# usbtinyisp.net
KiCad netlist of a schematic drawn in EAGLE
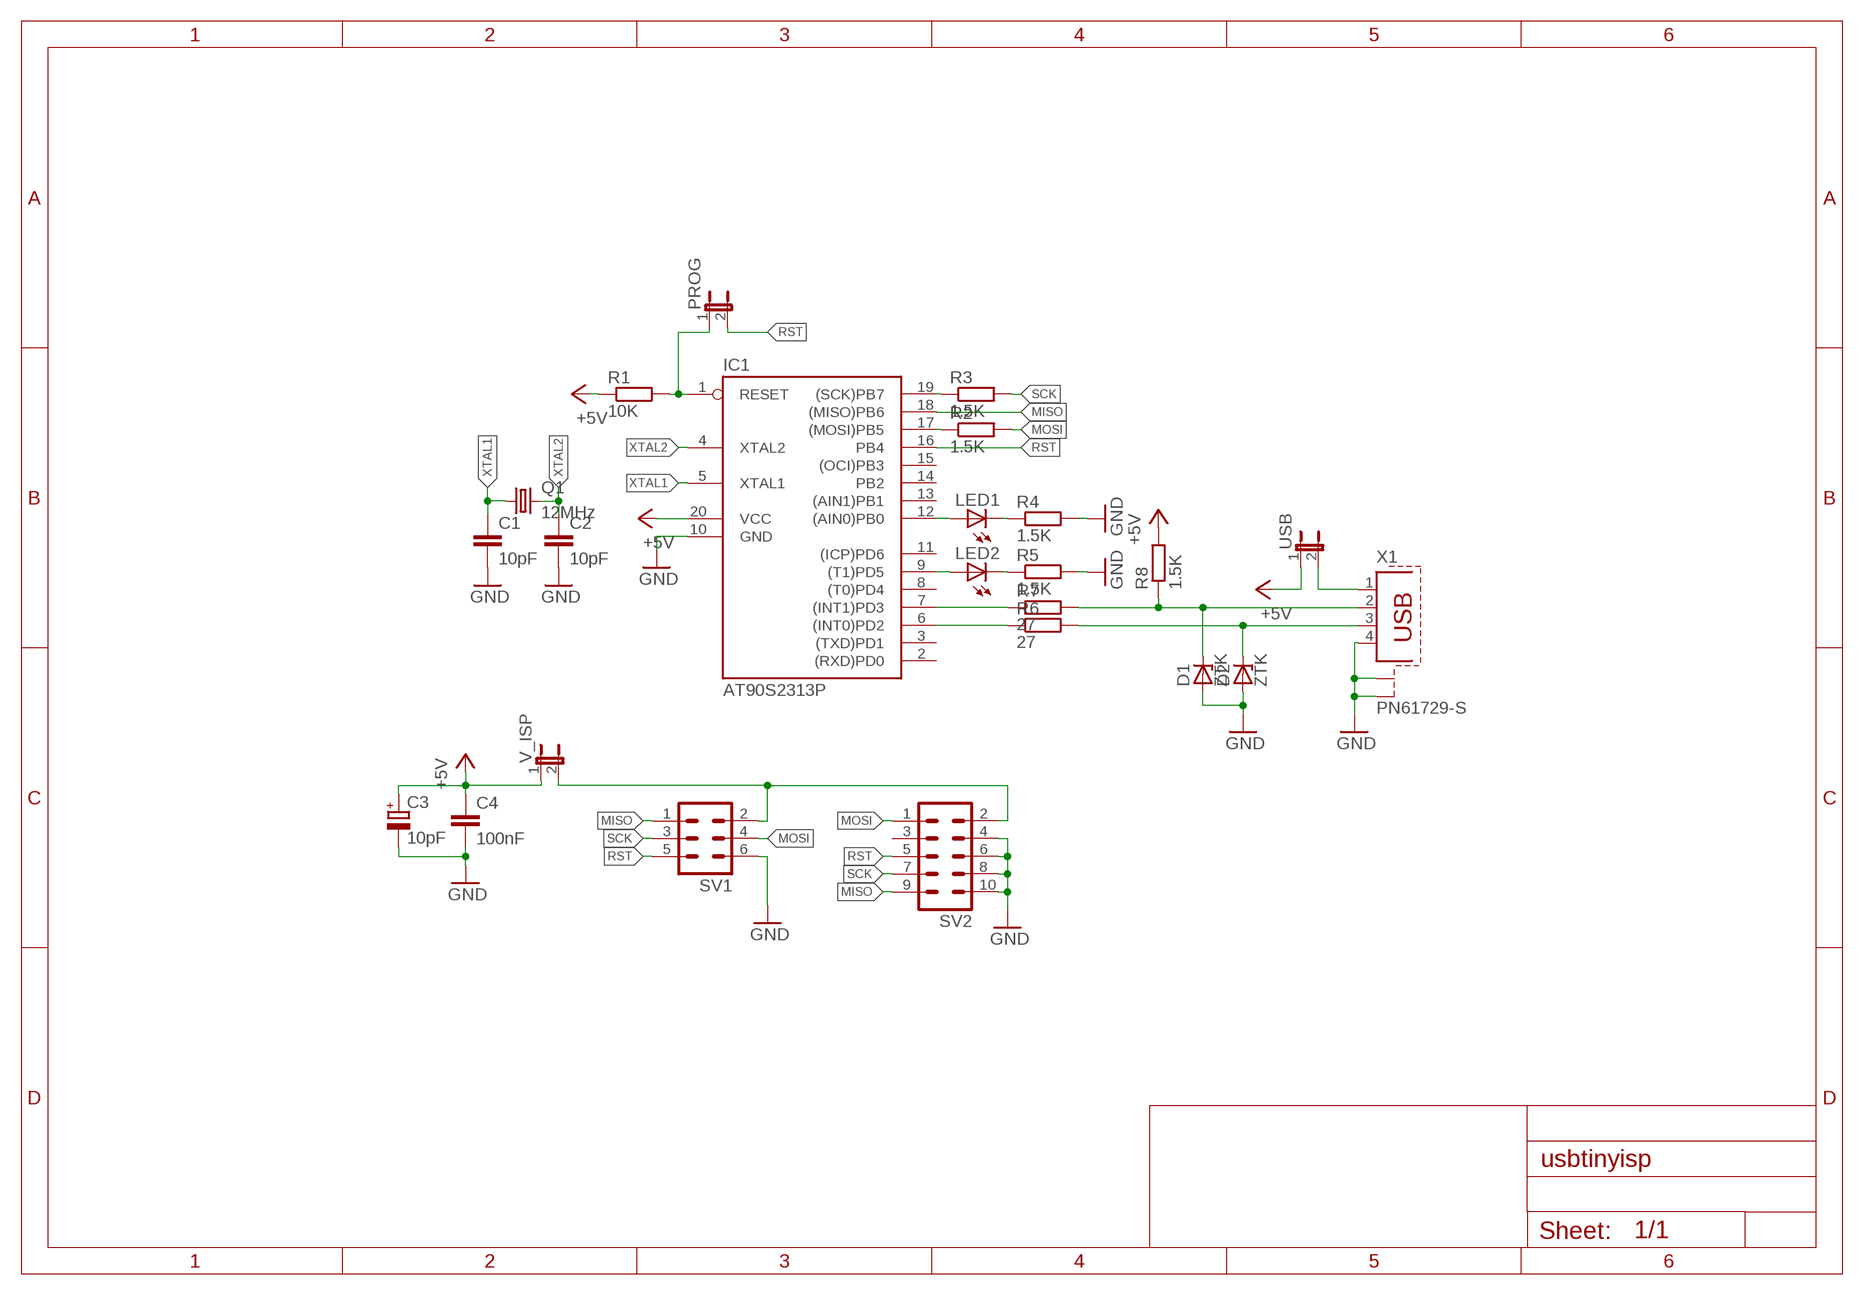
[diagram p0: schematic, sheet 1]

(export (version "E")
  (design (tool "Eeschema 10.0.6"))
  (components
    (comp (ref "C1")
      (value "10pF")
      (footprint "eagle-import:C025-025X050")
      (libsource (lib "eagle-import") (part "C-EU025-025X050"))
    )
    (comp (ref "C2")
      (value "10pF")
      (footprint "eagle-import:C025-025X050")
      (libsource (lib "eagle-import") (part "C-EU025-025X050"))
    )
    (comp (ref "C3")
      (value "10pF")
      (footprint "eagle-import:E2,5-6E")
      (libsource (lib "eagle-import") (part "CPOL-EUE2,5-6E"))
    )
    (comp (ref "C4")
      (value "100nF")
      (footprint "eagle-import:C025-025X050")
      (libsource (lib "eagle-import") (part "C-EU025-025X050"))
    )
    (comp (ref "D1")
      (value "ZTK")
      (footprint "eagle-import:DO35Z10")
      (libsource (lib "eagle-import") (part "ZTK"))
    )
    (comp (ref "D2")
      (value "ZTK")
      (footprint "eagle-import:DO35Z10")
      (libsource (lib "eagle-import") (part "ZTK"))
    )
    (comp (ref "IC1")
      (value "AT90S2313P")
      (footprint "eagle-import:DIL20")
      (libsource (lib "eagle-import") (part "AT90S2313P"))
    )
    (comp (ref "LED1")
      (value "LED3MM")
      (footprint "eagle-import:LED3MM")
      (libsource (lib "eagle-import") (part "LED3MM"))
    )
    (comp (ref "LED2")
      (value "LED3MM")
      (footprint "eagle-import:LED3MM")
      (libsource (lib "eagle-import") (part "LED3MM"))
    )
    (comp (ref "PROG")
      (value "JP1E")
      (footprint "eagle-import:JP1")
      (libsource (lib "eagle-import") (part "JP1E"))
    )
    (comp (ref "Q1")
      (value "12MHz")
      (footprint "eagle-import:HC49U70")
      (libsource (lib "eagle-import") (part "CRYSTALHC49U70"))
    )
    (comp (ref "R1")
      (value "10K")
      (footprint "eagle-import:0207_7")
      (libsource (lib "eagle-import") (part "R-EU_0207/7"))
    )
    (comp (ref "R2")
      (value "1.5K")
      (footprint "eagle-import:0207_7")
      (libsource (lib "eagle-import") (part "R-EU_0207/7"))
    )
    (comp (ref "R3")
      (value "1.5K")
      (footprint "eagle-import:0207_7")
      (libsource (lib "eagle-import") (part "R-EU_0207/7"))
    )
    (comp (ref "R4")
      (value "1.5K")
      (footprint "eagle-import:0207_7")
      (libsource (lib "eagle-import") (part "R-EU_0207/7"))
    )
    (comp (ref "R5")
      (value "1.5K")
      (footprint "eagle-import:0207_7")
      (libsource (lib "eagle-import") (part "R-EU_0207/7"))
    )
    (comp (ref "R6")
      (value "27")
      (footprint "eagle-import:0207_7")
      (libsource (lib "eagle-import") (part "R-EU_0207/7"))
    )
    (comp (ref "R7")
      (value "27")
      (footprint "eagle-import:0207_7")
      (libsource (lib "eagle-import") (part "R-EU_0207/7"))
    )
    (comp (ref "R8")
      (value "1.5K")
      (footprint "eagle-import:0207_7")
      (libsource (lib "eagle-import") (part "R-EU_0207/7"))
    )
    (comp (ref "SV1")
      (value "MA03-2")
      (footprint "eagle-import:MA03-2")
      (libsource (lib "eagle-import") (part "MA03-2"))
    )
    (comp (ref "SV2")
      (value "MA05-2")
      (footprint "eagle-import:MA05-2")
      (libsource (lib "eagle-import") (part "MA05-2"))
    )
    (comp (ref "USB")
      (value "JP1E")
      (footprint "eagle-import:JP1")
      (libsource (lib "eagle-import") (part "JP1E"))
    )
    (comp (ref "V_ISP")
      (value "JP1E")
      (footprint "eagle-import:JP1")
      (libsource (lib "eagle-import") (part "JP1E"))
    )
    (comp (ref "X1")
      (value "PN61729-S")
      (footprint "eagle-import:PN61729-S")
      (libsource (lib "eagle-import") (part "PN61729-S"))
    )
  )
  (nets
    (net (code "1") (name "+5V") (class "Default")
      (node (ref "C3") (pin "+") (pinfunction "+_+") (pintype "passive"))
      (node (ref "C4") (pin "1") (pinfunction "1_1") (pintype "passive"))
      (node (ref "IC1") (pin "20") (pinfunction "VCC_20") (pintype "power_in"))
      (node (ref "R1") (pin "1") (pinfunction "1_1") (pintype "passive"))
      (node (ref "R8") (pin "2") (pinfunction "2_2") (pintype "passive"))
      (node (ref "USB") (pin "1") (pinfunction "1_1") (pintype "passive"))
      (node (ref "V_ISP") (pin "1") (pinfunction "1_1") (pintype "passive"))
    )
    (net (code "2") (name "GND") (class "Default")
      (node (ref "C1") (pin "2") (pinfunction "2_2") (pintype "passive"))
      (node (ref "C2") (pin "2") (pinfunction "2_2") (pintype "passive"))
      (node (ref "C3") (pin "-") (pinfunction "-_-") (pintype "passive"))
      (node (ref "C4") (pin "2") (pinfunction "2_2") (pintype "passive"))
      (node (ref "D1") (pin "A") (pinfunction "A_A") (pintype "passive"))
      (node (ref "D2") (pin "A") (pinfunction "A_A") (pintype "passive"))
      (node (ref "IC1") (pin "10") (pinfunction "GND_10") (pintype "power_in"))
      (node (ref "R4") (pin "2") (pinfunction "2_2") (pintype "passive"))
      (node (ref "R5") (pin "2") (pinfunction "2_2") (pintype "passive"))
      (node (ref "SV1") (pin "6") (pinfunction "6_6") (pintype "passive"))
      (node (ref "SV2") (pin "10") (pinfunction "10_10") (pintype "passive"))
      (node (ref "SV2") (pin "4") (pinfunction "4_4") (pintype "passive"))
      (node (ref "SV2") (pin "6") (pinfunction "6_6") (pintype "passive"))
      (node (ref "SV2") (pin "8") (pinfunction "8_8") (pintype "passive"))
      (node (ref "X1") (pin "4") (pinfunction "4_4") (pintype "passive"))
      (node (ref "X1") (pin "S1") (pinfunction "S1_S1") (pintype "passive"))
      (node (ref "X1") (pin "S2") (pinfunction "S2_S2") (pintype "passive"))
    )
    (net (code "3") (name "MISO") (class "Default")
      (node (ref "IC1") (pin "18") (pinfunction "(MISO)PB6_18") (pintype "bidirectional"))
      (node (ref "SV1") (pin "1") (pinfunction "1_1") (pintype "passive"))
      (node (ref "SV2") (pin "9") (pinfunction "9_9") (pintype "passive"))
    )
    (net (code "4") (name "MOSI") (class "Default")
      (node (ref "R2") (pin "2") (pinfunction "2_2") (pintype "passive"))
      (node (ref "SV1") (pin "4") (pinfunction "4_4") (pintype "passive"))
      (node (ref "SV2") (pin "1") (pinfunction "1_1") (pintype "passive"))
    )
    (net (code "5") (name "Net-(D1-PadC)") (class "Default")
      (node (ref "D1") (pin "C") (pinfunction "C_C") (pintype "passive"))
      (node (ref "R7") (pin "2") (pinfunction "2_2") (pintype "passive"))
      (node (ref "R8") (pin "1") (pinfunction "1_1") (pintype "passive"))
      (node (ref "X1") (pin "2") (pinfunction "2_2") (pintype "passive"))
    )
    (net (code "6") (name "Net-(D2-PadC)") (class "Default")
      (node (ref "D2") (pin "C") (pinfunction "C_C") (pintype "passive"))
      (node (ref "R6") (pin "2") (pinfunction "2_2") (pintype "passive"))
      (node (ref "X1") (pin "3") (pinfunction "3_3") (pintype "passive"))
    )
    (net (code "7") (name "Net-(IC1-(AIN0)PB0)") (class "Default")
      (node (ref "IC1") (pin "12") (pinfunction "(AIN0)PB0_12") (pintype "bidirectional"))
      (node (ref "LED1") (pin "A") (pinfunction "A_A") (pintype "passive"))
    )
    (net (code "8") (name "Net-(IC1-(INT0)PD2)") (class "Default")
      (node (ref "IC1") (pin "6") (pinfunction "(INT0)PD2_6") (pintype "bidirectional"))
      (node (ref "R6") (pin "1") (pinfunction "1_1") (pintype "passive"))
    )
    (net (code "9") (name "Net-(IC1-(INT1)PD3)") (class "Default")
      (node (ref "IC1") (pin "7") (pinfunction "(INT1)PD3_7") (pintype "bidirectional"))
      (node (ref "R7") (pin "1") (pinfunction "1_1") (pintype "passive"))
    )
    (net (code "10") (name "Net-(IC1-(MOSI)PB5)") (class "Default")
      (node (ref "IC1") (pin "17") (pinfunction "(MOSI)PB5_17") (pintype "bidirectional"))
      (node (ref "R2") (pin "1") (pinfunction "1_1") (pintype "passive"))
    )
    (net (code "11") (name "Net-(IC1-(SCK)PB7)") (class "Default")
      (node (ref "IC1") (pin "19") (pinfunction "(SCK)PB7_19") (pintype "bidirectional"))
      (node (ref "R3") (pin "1") (pinfunction "1_1") (pintype "passive"))
    )
    (net (code "12") (name "Net-(IC1-(T1)PD5)") (class "Default")
      (node (ref "IC1") (pin "9") (pinfunction "(T1)PD5_9") (pintype "bidirectional"))
      (node (ref "LED2") (pin "A") (pinfunction "A_A") (pintype "passive"))
    )
    (net (code "13") (name "Net-(IC1-RESET)") (class "Default")
      (node (ref "IC1") (pin "1") (pinfunction "RESET_1") (pintype "bidirectional"))
      (node (ref "PROG") (pin "1") (pinfunction "1_1") (pintype "passive"))
      (node (ref "R1") (pin "2") (pinfunction "2_2") (pintype "passive"))
    )
    (net (code "14") (name "Net-(LED1-C)") (class "Default")
      (node (ref "LED1") (pin "K") (pinfunction "C_K") (pintype "passive"))
      (node (ref "R4") (pin "1") (pinfunction "1_1") (pintype "passive"))
    )
    (net (code "15") (name "Net-(LED2-C)") (class "Default")
      (node (ref "LED2") (pin "K") (pinfunction "C_K") (pintype "passive"))
      (node (ref "R5") (pin "1") (pinfunction "1_1") (pintype "passive"))
    )
    (net (code "16") (name "Net-(SV1-Pad2)") (class "Default")
      (node (ref "SV1") (pin "2") (pinfunction "2_2") (pintype "passive"))
      (node (ref "SV2") (pin "2") (pinfunction "2_2") (pintype "passive"))
      (node (ref "V_ISP") (pin "2") (pinfunction "2_2") (pintype "passive"))
    )
    (net (code "17") (name "Net-(USB-Pad2)") (class "Default")
      (node (ref "USB") (pin "2") (pinfunction "2_2") (pintype "passive"))
      (node (ref "X1") (pin "1") (pinfunction "1_1") (pintype "passive"))
    )
    (net (code "18") (name "RST") (class "Default")
      (node (ref "IC1") (pin "16") (pinfunction "PB4_16") (pintype "bidirectional"))
      (node (ref "PROG") (pin "2") (pinfunction "2_2") (pintype "passive"))
      (node (ref "SV1") (pin "5") (pinfunction "5_5") (pintype "passive"))
      (node (ref "SV2") (pin "5") (pinfunction "5_5") (pintype "passive"))
    )
    (net (code "19") (name "SCK") (class "Default")
      (node (ref "R3") (pin "2") (pinfunction "2_2") (pintype "passive"))
      (node (ref "SV1") (pin "3") (pinfunction "3_3") (pintype "passive"))
      (node (ref "SV2") (pin "7") (pinfunction "7_7") (pintype "passive"))
    )
    (net (code "20") (name "XTAL1") (class "Default")
      (node (ref "C1") (pin "1") (pinfunction "1_1") (pintype "passive"))
      (node (ref "IC1") (pin "5") (pinfunction "XTAL1_5") (pintype "bidirectional"))
      (node (ref "Q1") (pin "1") (pinfunction "1_1") (pintype "passive"))
    )
    (net (code "21") (name "XTAL2") (class "Default")
      (node (ref "C2") (pin "1") (pinfunction "1_1") (pintype "passive"))
      (node (ref "IC1") (pin "4") (pinfunction "XTAL2_4") (pintype "bidirectional"))
      (node (ref "Q1") (pin "2") (pinfunction "2_2") (pintype "passive"))
    )
    (net (code "22") (name "unconnected-(IC1-(AIN1)PB1-Pad13)") (class "Default")
      (node (ref "IC1") (pin "13") (pinfunction "(AIN1)PB1_13") (pintype "bidirectional"))
    )
    (net (code "23") (name "unconnected-(IC1-(ICP)PD6-Pad11)") (class "Default")
      (node (ref "IC1") (pin "11") (pinfunction "(ICP)PD6_11") (pintype "bidirectional"))
    )
    (net (code "24") (name "unconnected-(IC1-(OCI)PB3-Pad15)") (class "Default")
      (node (ref "IC1") (pin "15") (pinfunction "(OCI)PB3_15") (pintype "bidirectional"))
    )
    (net (code "25") (name "unconnected-(IC1-(RXD)PD0-Pad2)") (class "Default")
      (node (ref "IC1") (pin "2") (pinfunction "(RXD)PD0_2") (pintype "bidirectional"))
    )
    (net (code "26") (name "unconnected-(IC1-(T0)PD4-Pad8)") (class "Default")
      (node (ref "IC1") (pin "8") (pinfunction "(T0)PD4_8") (pintype "bidirectional"))
    )
    (net (code "27") (name "unconnected-(IC1-(TXD)PD1-Pad3)") (class "Default")
      (node (ref "IC1") (pin "3") (pinfunction "(TXD)PD1_3") (pintype "bidirectional"))
    )
    (net (code "28") (name "unconnected-(IC1-PB2-Pad14)") (class "Default")
      (node (ref "IC1") (pin "14") (pinfunction "PB2_14") (pintype "bidirectional"))
    )
    (net (code "29") (name "unconnected-(SV2-Pad3)") (class "Default")
      (node (ref "SV2") (pin "3") (pinfunction "3_3") (pintype "passive"))
    )
  )
)
